# Block_Diagram_V1.net
KiCad netlist of a schematic drawn in EAGLE
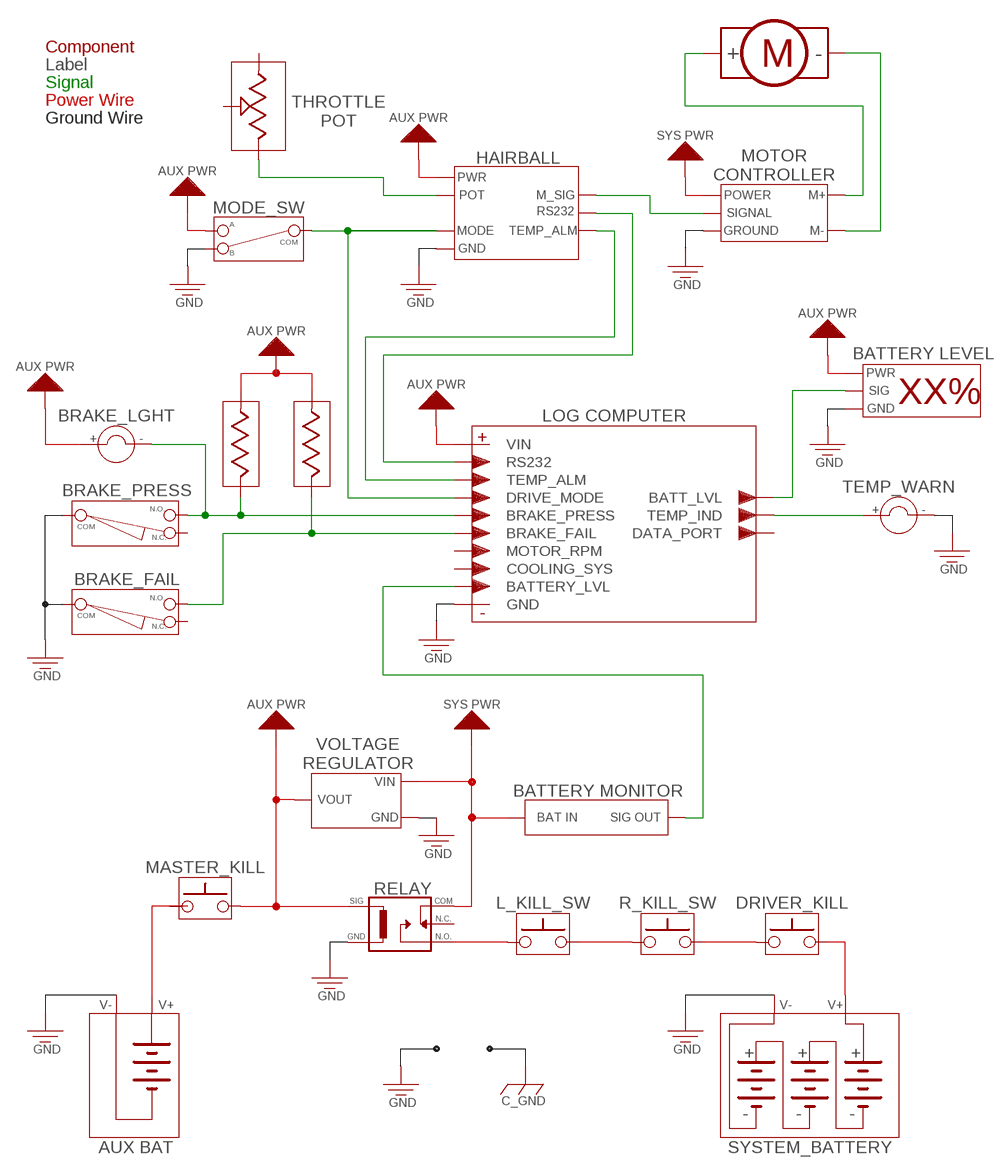
[diagram p0: schematic, sheet 1]

(export (version "E")
  (design (tool "Eeschema 10.0.6"))
  (components
    (comp (ref "BRAKE_FAIL")
      (value "LIMIT_SWITCH")
      (footprint "eagle-import:LIMIT_SWITCH")
      (libsource (lib "eagle-import") (part "LIMIT_SWITCH"))
    )
    (comp (ref "BRAKE_LGHT")
      (value "LIGHT")
      (footprint "eagle-import:LIGHT")
      (libsource (lib "eagle-import") (part "LIGHT"))
    )
    (comp (ref "BRAKE_PRESS")
      (value "LIMIT_SWITCH")
      (footprint "eagle-import:LIMIT_SWITCH")
      (libsource (lib "eagle-import") (part "LIMIT_SWITCH"))
    )
    (comp (ref "DRIVER_KILL")
      (value "BUTTON_SWITCH")
      (footprint "eagle-import:BUTTON_SWITCH")
      (libsource (lib "eagle-import") (part "BUTTON_SWITCH"))
    )
    (comp (ref "L_KILL_SW")
      (value "BUTTON_SWITCH")
      (footprint "eagle-import:BUTTON_SWITCH")
      (libsource (lib "eagle-import") (part "BUTTON_SWITCH"))
    )
    (comp (ref "MASTER_KILL")
      (value "BUTTON_SWITCH")
      (footprint "eagle-import:BUTTON_SWITCH")
      (libsource (lib "eagle-import") (part "BUTTON_SWITCH"))
    )
    (comp (ref "MODE_SW")
      (value "TOGGLE_SWITCH")
      (footprint "eagle-import:TOGGLE_SWITCH")
      (libsource (lib "eagle-import") (part "TOGGLE_SWITCH"))
    )
    (comp (ref "R_KILL_SW")
      (value "BUTTON_SWITCH")
      (footprint "eagle-import:BUTTON_SWITCH")
      (libsource (lib "eagle-import") (part "BUTTON_SWITCH"))
    )
    (comp (ref "TEMP_WARN")
      (value "LIGHT")
      (footprint "eagle-import:LIGHT")
      (libsource (lib "eagle-import") (part "LIGHT"))
    )
    (comp (ref "U$1")
      (value "COMPUTER")
      (footprint "eagle-import:COMPUTER")
      (libsource (lib "eagle-import") (part "COMPUTER"))
    )
    (comp (ref "U$2")
      (value "SYSTEM_BAT")
      (footprint "eagle-import:SYSTEM_BAT")
      (libsource (lib "eagle-import") (part "SYSTEM_BAT"))
    )
    (comp (ref "U$3")
      (value "DC_MOTOR")
      (footprint "eagle-import:DC_MOTOR")
      (libsource (lib "eagle-import") (part "DC_MOTOR"))
    )
    (comp (ref "U$4")
      (value "MOTOR_CONTROLLER")
      (footprint "eagle-import:MOTOR_CONTROLLER")
      (libsource (lib "eagle-import") (part "MOTOR_CONTROLLER"))
    )
    (comp (ref "U$5")
      (value "HAIRBALL")
      (footprint "eagle-import:HAIRBALL")
      (libsource (lib "eagle-import") (part "HAIRBALL"))
    )
    (comp (ref "U$6")
      (value "AUX_PWR")
      (footprint "eagle-import:AUX_PWR")
      (libsource (lib "eagle-import") (part "AUX_PWR"))
    )
    (comp (ref "U$7")
      (value "12V_BAT")
      (footprint "eagle-import:12V_BAT")
      (libsource (lib "eagle-import") (part "12V_BAT"))
    )
    (comp (ref "U$8")
      (value "RELAY")
      (footprint "eagle-import:RELAY")
      (libsource (lib "eagle-import") (part "RELAY"))
    )
    (comp (ref "U$9")
      (value "CHASSIS_GND")
      (footprint "eagle-import:CHASSIS_GND")
      (libsource (lib "eagle-import") (part "CHASSIS_GND"))
    )
    (comp (ref "U$10")
      (value "GND")
      (footprint "eagle-import:GND")
      (libsource (lib "eagle-import") (part "GND"))
    )
    (comp (ref "U$11")
      (value "GND")
      (footprint "eagle-import:GND")
      (libsource (lib "eagle-import") (part "GND"))
    )
    (comp (ref "U$12")
      (value "GND")
      (footprint "eagle-import:GND")
      (libsource (lib "eagle-import") (part "GND"))
    )
    (comp (ref "U$13")
      (value "GND")
      (footprint "eagle-import:GND")
      (libsource (lib "eagle-import") (part "GND"))
    )
    (comp (ref "U$15")
      (value "V_SYS")
      (footprint "eagle-import:V_SYS")
      (libsource (lib "eagle-import") (part "V_SYS"))
    )
    (comp (ref "U$16")
      (value "VOLTAGE_REGULATOR")
      (footprint "eagle-import:VOLTAGE_REGULATOR")
      (libsource (lib "eagle-import") (part "VOLTAGE_REGULATOR"))
    )
    (comp (ref "U$17")
      (value "GND")
      (footprint "eagle-import:GND")
      (libsource (lib "eagle-import") (part "GND"))
    )
    (comp (ref "U$20")
      (value "AUX_PWR")
      (footprint "eagle-import:AUX_PWR")
      (libsource (lib "eagle-import") (part "AUX_PWR"))
    )
    (comp (ref "U$21")
      (value "GND")
      (footprint "eagle-import:GND")
      (libsource (lib "eagle-import") (part "GND"))
    )
    (comp (ref "U$22")
      (value "AUX_PWR")
      (footprint "eagle-import:AUX_PWR")
      (libsource (lib "eagle-import") (part "AUX_PWR"))
    )
    (comp (ref "U$23")
      (value "GND")
      (footprint "eagle-import:GND")
      (libsource (lib "eagle-import") (part "GND"))
    )
    (comp (ref "U$24")
      (value "V_SYS")
      (footprint "eagle-import:V_SYS")
      (libsource (lib "eagle-import") (part "V_SYS"))
    )
    (comp (ref "U$25")
      (value "GND")
      (footprint "eagle-import:GND")
      (libsource (lib "eagle-import") (part "GND"))
    )
    (comp (ref "U$26")
      (value "BATTERY_MONITOR")
      (footprint "eagle-import:BATTERY_MONITOR")
      (libsource (lib "eagle-import") (part "BATTERY_MONITOR"))
    )
    (comp (ref "U$28")
      (value "THROTTLE_POT")
      (footprint "eagle-import:THROTTLE_POT")
      (libsource (lib "eagle-import") (part "THROTTLE_POT"))
    )
    (comp (ref "U$29")
      (value "AUX_PWR")
      (footprint "eagle-import:AUX_PWR")
      (libsource (lib "eagle-import") (part "AUX_PWR"))
    )
    (comp (ref "U$30")
      (value "GND")
      (footprint "eagle-import:GND")
      (libsource (lib "eagle-import") (part "GND"))
    )
    (comp (ref "U$31")
      (value "AUX_PWR")
      (footprint "eagle-import:AUX_PWR")
      (libsource (lib "eagle-import") (part "AUX_PWR"))
    )
    (comp (ref "U$32")
      (value "RESISTOR")
      (footprint "eagle-import:RESISTOR")
      (libsource (lib "eagle-import") (part "RESISTOR"))
    )
    (comp (ref "U$33")
      (value "RESISTOR")
      (footprint "eagle-import:RESISTOR")
      (libsource (lib "eagle-import") (part "RESISTOR"))
    )
    (comp (ref "U$35")
      (value "GND")
      (footprint "eagle-import:GND")
      (libsource (lib "eagle-import") (part "GND"))
    )
    (comp (ref "U$36")
      (value "BATTERY_DISPLAY")
      (footprint "eagle-import:BATTERY_DISPLAY")
      (libsource (lib "eagle-import") (part "BATTERY_DISPLAY"))
    )
    (comp (ref "U$37")
      (value "AUX_PWR")
      (footprint "eagle-import:AUX_PWR")
      (libsource (lib "eagle-import") (part "AUX_PWR"))
    )
    (comp (ref "U$38")
      (value "GND")
      (footprint "eagle-import:GND")
      (libsource (lib "eagle-import") (part "GND"))
    )
    (comp (ref "U$40")
      (value "GND")
      (footprint "eagle-import:GND")
      (libsource (lib "eagle-import") (part "GND"))
    )
    (comp (ref "U$41")
      (value "AUX_PWR")
      (footprint "eagle-import:AUX_PWR")
      (libsource (lib "eagle-import") (part "AUX_PWR"))
    )
  )
  (nets
    (net (code "1") (name "Net-(BRAKE_FAIL-PadNO)") (class "Default")
      (node (ref "BRAKE_FAIL") (pin "NO") (pinfunction "NO_NO") (pintype "bidirectional"))
      (node (ref "U$1") (pin "BRAKE_FAIL") (pinfunction "BRAKE_FAIL_BRAKE_FAIL") (pintype "bidirectional"))
      (node (ref "U$33") (pin "B") (pinfunction "B_B") (pintype "passive"))
    )
    (net (code "2") (name "Net-(BRAKE_LGHT-PadGND)") (class "Default")
      (node (ref "BRAKE_LGHT") (pin "GND") (pinfunction "GND_GND") (pintype "bidirectional"))
      (node (ref "BRAKE_PRESS") (pin "NO") (pinfunction "NO_NO") (pintype "bidirectional"))
      (node (ref "U$1") (pin "BRAKE_PRESS") (pinfunction "BRAKE_PRESS_BRAKE_PRESS") (pintype "bidirectional"))
      (node (ref "U$32") (pin "B") (pinfunction "B_B") (pintype "passive"))
    )
    (net (code "3") (name "Net-(MODE_SW-PadCOM)") (class "Default")
      (node (ref "MODE_SW") (pin "COM") (pinfunction "COM_COM") (pintype "bidirectional"))
      (node (ref "U$1") (pin "DRIVE_MODE") (pinfunction "DRIVE_MODE_DRIVE_MODE") (pintype "bidirectional"))
      (node (ref "U$5") (pin "MODE") (pinfunction "MODE_MODE") (pintype "bidirectional"))
    )
    (net (code "4") (name "Net-(TEMP_WARN-PadVIN)") (class "Default")
      (node (ref "TEMP_WARN") (pin "VIN") (pinfunction "VIN_VIN") (pintype "bidirectional"))
      (node (ref "U$1") (pin "TEMP_IND") (pinfunction "TEMP_IND_TEMP_IND") (pintype "bidirectional"))
    )
    (net (code "5") (name "Net-(U$1-PadBATTERY_LVL)") (class "Default")
      (node (ref "U$1") (pin "BATTERY_LVL") (pinfunction "BATTERY_LVL_BATTERY_LVL") (pintype "bidirectional"))
      (node (ref "U$26") (pin "SIG") (pinfunction "SIG_SIG") (pintype "bidirectional"))
    )
    (net (code "6") (name "Net-(U$1-PadBATT_LVL)") (class "Default")
      (node (ref "U$1") (pin "BATT_LVL") (pinfunction "BATT_LVL_BATT_LVL") (pintype "bidirectional"))
      (node (ref "U$36") (pin "SIG") (pinfunction "SIG_SIG") (pintype "bidirectional"))
    )
    (net (code "7") (name "Net-(U$1-PadRS232)") (class "Default")
      (node (ref "U$1") (pin "RS232") (pinfunction "RS232_RS232") (pintype "bidirectional"))
      (node (ref "U$5") (pin "RS232") (pinfunction "RS232_RS232") (pintype "bidirectional"))
    )
    (net (code "8") (name "Net-(U$1-PadTEMP_ALM)") (class "Default")
      (node (ref "U$1") (pin "TEMP_ALM") (pinfunction "TEMP_ALM_TEMP_ALM") (pintype "bidirectional"))
      (node (ref "U$5") (pin "OVERTEMP") (pinfunction "OVERTEMP_OVERTEMP") (pintype "bidirectional"))
    )
    (net (code "9") (name "Net-(U$3-Pad+)") (class "Default")
      (node (ref "U$3") (pin "+") (pinfunction "+_+") (pintype "bidirectional"))
      (node (ref "U$4") (pin "M+") (pinfunction "M+_M+") (pintype "bidirectional"))
    )
    (net (code "10") (name "Net-(U$3-Pad-)") (class "Default")
      (node (ref "U$3") (pin "-") (pinfunction "-_-") (pintype "bidirectional"))
      (node (ref "U$4") (pin "M-") (pinfunction "M-_M-") (pintype "bidirectional"))
    )
    (net (code "11") (name "Net-(U$5-MOTOR_SIG)") (class "Default")
      (node (ref "U$4") (pin "SIG") (pinfunction "SIG_SIG") (pintype "bidirectional"))
      (node (ref "U$5") (pin "M_SIG") (pinfunction "MOTOR_SIG_M_SIG") (pintype "bidirectional"))
    )
    (net (code "12") (name "Net-(U$28-PadV-)") (class "Default")
      (node (ref "U$28") (pin "V-") (pinfunction "V-_V-") (pintype "passive"))
      (node (ref "U$5") (pin "THROTTLE_POT") (pinfunction "THROTTLE_POT_THROTTLE_POT") (pintype "bidirectional"))
    )
    (net (code "13") (name "unconnected-(BRAKE_FAIL-PadCOM)") (class "Default")
      (node (ref "BRAKE_FAIL") (pin "COM") (pinfunction "COM_COM") (pintype "bidirectional"))
    )
    (net (code "14") (name "unconnected-(BRAKE_FAIL-PadNC)") (class "Default")
      (node (ref "BRAKE_FAIL") (pin "NC") (pinfunction "NC_NC") (pintype "bidirectional"))
    )
    (net (code "15") (name "unconnected-(BRAKE_LGHT-PadVIN)") (class "Default")
      (node (ref "BRAKE_LGHT") (pin "VIN") (pinfunction "VIN_VIN") (pintype "bidirectional"))
    )
    (net (code "16") (name "unconnected-(BRAKE_PRESS-PadCOM)") (class "Default")
      (node (ref "BRAKE_PRESS") (pin "COM") (pinfunction "COM_COM") (pintype "bidirectional"))
    )
    (net (code "17") (name "unconnected-(BRAKE_PRESS-PadNC)") (class "Default")
      (node (ref "BRAKE_PRESS") (pin "NC") (pinfunction "NC_NC") (pintype "bidirectional"))
    )
    (net (code "18") (name "unconnected-(DRIVER_KILL-PadA)") (class "Default")
      (node (ref "DRIVER_KILL") (pin "A") (pinfunction "A_A") (pintype "bidirectional"))
    )
    (net (code "19") (name "unconnected-(DRIVER_KILL-PadB)") (class "Default")
      (node (ref "DRIVER_KILL") (pin "B") (pinfunction "B_B") (pintype "bidirectional"))
    )
    (net (code "20") (name "unconnected-(L_KILL_SW-PadA)") (class "Default")
      (node (ref "L_KILL_SW") (pin "A") (pinfunction "A_A") (pintype "bidirectional"))
    )
    (net (code "21") (name "unconnected-(L_KILL_SW-PadB)") (class "Default")
      (node (ref "L_KILL_SW") (pin "B") (pinfunction "B_B") (pintype "bidirectional"))
    )
    (net (code "22") (name "unconnected-(MASTER_KILL-PadA)") (class "Default")
      (node (ref "MASTER_KILL") (pin "A") (pinfunction "A_A") (pintype "bidirectional"))
    )
    (net (code "23") (name "unconnected-(MASTER_KILL-PadB)") (class "Default")
      (node (ref "MASTER_KILL") (pin "B") (pinfunction "B_B") (pintype "bidirectional"))
    )
    (net (code "24") (name "unconnected-(MODE_SW-PadPOS_A)") (class "Default")
      (node (ref "MODE_SW") (pin "POS_A") (pinfunction "POS_A_POS_A") (pintype "bidirectional"))
    )
    (net (code "25") (name "unconnected-(MODE_SW-PadPOS_B)") (class "Default")
      (node (ref "MODE_SW") (pin "POS_B") (pinfunction "POS_B_POS_B") (pintype "bidirectional"))
    )
    (net (code "26") (name "unconnected-(R_KILL_SW-PadA)") (class "Default")
      (node (ref "R_KILL_SW") (pin "A") (pinfunction "A_A") (pintype "bidirectional"))
    )
    (net (code "27") (name "unconnected-(R_KILL_SW-PadB)") (class "Default")
      (node (ref "R_KILL_SW") (pin "B") (pinfunction "B_B") (pintype "bidirectional"))
    )
    (net (code "28") (name "unconnected-(TEMP_WARN-PadGND)") (class "Default")
      (node (ref "TEMP_WARN") (pin "GND") (pinfunction "GND_GND") (pintype "bidirectional"))
    )
    (net (code "29") (name "unconnected-(U$1-DATA_PORT-PadDATAPORT)") (class "Default")
      (node (ref "U$1") (pin "DATAPORT") (pinfunction "DATA_PORT_DATAPORT") (pintype "bidirectional"))
    )
    (net (code "30") (name "unconnected-(U$1-PadCOOLING_SYS)") (class "Default")
      (node (ref "U$1") (pin "COOLING_SYS") (pinfunction "COOLING_SYS_COOLING_SYS") (pintype "bidirectional"))
    )
    (net (code "31") (name "unconnected-(U$1-PadGND)") (class "Default")
      (node (ref "U$1") (pin "GND") (pinfunction "GND_GND") (pintype "bidirectional"))
    )
    (net (code "32") (name "unconnected-(U$1-PadMOTOR_RPM)") (class "Default")
      (node (ref "U$1") (pin "MOTOR_RPM") (pinfunction "MOTOR_RPM_MOTOR_RPM") (pintype "bidirectional"))
    )
    (net (code "33") (name "unconnected-(U$1-VIN-PadPWR)") (class "Default")
      (node (ref "U$1") (pin "PWR") (pinfunction "VIN_PWR") (pintype "bidirectional"))
    )
    (net (code "34") (name "unconnected-(U$2-PadV+)") (class "Default")
      (node (ref "U$2") (pin "V+") (pinfunction "V+_V+") (pintype "passive"))
    )
    (net (code "35") (name "unconnected-(U$2-PadV-)") (class "Default")
      (node (ref "U$2") (pin "V-") (pinfunction "V-_V-") (pintype "passive"))
    )
    (net (code "36") (name "unconnected-(U$4-PadGND)") (class "Default")
      (node (ref "U$4") (pin "GND") (pinfunction "GND_GND") (pintype "bidirectional"))
    )
    (net (code "37") (name "unconnected-(U$4-PadPWR)") (class "Default")
      (node (ref "U$4") (pin "PWR") (pinfunction "PWR_PWR") (pintype "bidirectional"))
    )
    (net (code "38") (name "unconnected-(U$5-PadGND)") (class "Default")
      (node (ref "U$5") (pin "GND") (pinfunction "GND_GND") (pintype "bidirectional"))
    )
    (net (code "39") (name "unconnected-(U$5-PadPWR)") (class "Default")
      (node (ref "U$5") (pin "PWR") (pinfunction "PWR_PWR") (pintype "bidirectional"))
    )
    (net (code "40") (name "unconnected-(U$6-PadAUX_PWR)") (class "Default")
      (node (ref "U$6") (pin "AUX_PWR") (pinfunction "AUX_PWR_AUX_PWR") (pintype "bidirectional"))
    )
    (net (code "41") (name "unconnected-(U$7-Pad+12V)") (class "Default")
      (node (ref "U$7") (pin "+12V") (pinfunction "+12V_+12V") (pintype "bidirectional"))
    )
    (net (code "42") (name "unconnected-(U$7-PadGND)") (class "Default")
      (node (ref "U$7") (pin "GND") (pinfunction "GND_GND") (pintype "bidirectional"))
    )
    (net (code "43") (name "unconnected-(U$8-PadCOM)") (class "Default")
      (node (ref "U$8") (pin "COM") (pinfunction "COM_COM") (pintype "bidirectional"))
    )
    (net (code "44") (name "unconnected-(U$8-PadGND)") (class "Default")
      (node (ref "U$8") (pin "GND") (pinfunction "GND_GND") (pintype "bidirectional"))
    )
    (net (code "45") (name "unconnected-(U$8-PadNC)") (class "Default")
      (node (ref "U$8") (pin "NC") (pinfunction "NC_NC") (pintype "bidirectional"))
    )
    (net (code "46") (name "unconnected-(U$8-PadNO)") (class "Default")
      (node (ref "U$8") (pin "NO") (pinfunction "NO_NO") (pintype "bidirectional"))
    )
    (net (code "47") (name "unconnected-(U$8-PadSIG)") (class "Default")
      (node (ref "U$8") (pin "SIG") (pinfunction "SIG_SIG") (pintype "bidirectional"))
    )
    (net (code "48") (name "unconnected-(U$9-PadC_GND)") (class "Default")
      (node (ref "U$9") (pin "C_GND") (pinfunction "C_GND_C_GND") (pintype "bidirectional"))
    )
    (net (code "49") (name "unconnected-(U$10-PadGND)") (class "Default")
      (node (ref "U$10") (pin "GND") (pinfunction "GND_GND") (pintype "bidirectional"))
    )
    (net (code "50") (name "unconnected-(U$11-PadGND)") (class "Default")
      (node (ref "U$11") (pin "GND") (pinfunction "GND_GND") (pintype "bidirectional"))
    )
    (net (code "51") (name "unconnected-(U$12-PadGND)") (class "Default")
      (node (ref "U$12") (pin "GND") (pinfunction "GND_GND") (pintype "bidirectional"))
    )
    (net (code "52") (name "unconnected-(U$13-PadGND)") (class "Default")
      (node (ref "U$13") (pin "GND") (pinfunction "GND_GND") (pintype "bidirectional"))
    )
    (net (code "53") (name "unconnected-(U$15-PadV_SYS)") (class "Default")
      (node (ref "U$15") (pin "V_SYS") (pinfunction "V_SYS_V_SYS") (pintype "bidirectional"))
    )
    (net (code "54") (name "unconnected-(U$16-PadGND)") (class "Default")
      (node (ref "U$16") (pin "GND") (pinfunction "GND_GND") (pintype "bidirectional"))
    )
    (net (code "55") (name "unconnected-(U$16-PadVIN)") (class "Default")
      (node (ref "U$16") (pin "VIN") (pinfunction "VIN_VIN") (pintype "bidirectional"))
    )
    (net (code "56") (name "unconnected-(U$16-PadVOUT)") (class "Default")
      (node (ref "U$16") (pin "VOUT") (pinfunction "VOUT_VOUT") (pintype "bidirectional"))
    )
    (net (code "57") (name "unconnected-(U$17-PadGND)") (class "Default")
      (node (ref "U$17") (pin "GND") (pinfunction "GND_GND") (pintype "bidirectional"))
    )
    (net (code "58") (name "unconnected-(U$20-PadAUX_PWR)") (class "Default")
      (node (ref "U$20") (pin "AUX_PWR") (pinfunction "AUX_PWR_AUX_PWR") (pintype "bidirectional"))
    )
    (net (code "59") (name "unconnected-(U$21-PadGND)") (class "Default")
      (node (ref "U$21") (pin "GND") (pinfunction "GND_GND") (pintype "bidirectional"))
    )
    (net (code "60") (name "unconnected-(U$22-PadAUX_PWR)") (class "Default")
      (node (ref "U$22") (pin "AUX_PWR") (pinfunction "AUX_PWR_AUX_PWR") (pintype "bidirectional"))
    )
    (net (code "61") (name "unconnected-(U$23-PadGND)") (class "Default")
      (node (ref "U$23") (pin "GND") (pinfunction "GND_GND") (pintype "bidirectional"))
    )
    (net (code "62") (name "unconnected-(U$24-PadV_SYS)") (class "Default")
      (node (ref "U$24") (pin "V_SYS") (pinfunction "V_SYS_V_SYS") (pintype "bidirectional"))
    )
    (net (code "63") (name "unconnected-(U$25-PadGND)") (class "Default")
      (node (ref "U$25") (pin "GND") (pinfunction "GND_GND") (pintype "bidirectional"))
    )
    (net (code "64") (name "unconnected-(U$26-PadBAT)") (class "Default")
      (node (ref "U$26") (pin "BAT") (pinfunction "BAT_BAT") (pintype "bidirectional"))
    )
    (net (code "65") (name "unconnected-(U$28-PadADJ)") (class "Default")
      (node (ref "U$28") (pin "ADJ") (pinfunction "ADJ_ADJ") (pintype "passive"))
    )
    (net (code "66") (name "unconnected-(U$28-PadV+)") (class "Default")
      (node (ref "U$28") (pin "V+") (pinfunction "V+_V+") (pintype "passive"))
    )
    (net (code "67") (name "unconnected-(U$29-PadAUX_PWR)") (class "Default")
      (node (ref "U$29") (pin "AUX_PWR") (pinfunction "AUX_PWR_AUX_PWR") (pintype "bidirectional"))
    )
    (net (code "68") (name "unconnected-(U$30-PadGND)") (class "Default")
      (node (ref "U$30") (pin "GND") (pinfunction "GND_GND") (pintype "bidirectional"))
    )
    (net (code "69") (name "unconnected-(U$31-PadAUX_PWR)") (class "Default")
      (node (ref "U$31") (pin "AUX_PWR") (pinfunction "AUX_PWR_AUX_PWR") (pintype "bidirectional"))
    )
    (net (code "70") (name "unconnected-(U$32-PadA)") (class "Default")
      (node (ref "U$32") (pin "A") (pinfunction "A_A") (pintype "passive"))
    )
    (net (code "71") (name "unconnected-(U$33-PadA)") (class "Default")
      (node (ref "U$33") (pin "A") (pinfunction "A_A") (pintype "passive"))
    )
    (net (code "72") (name "unconnected-(U$35-PadGND)") (class "Default")
      (node (ref "U$35") (pin "GND") (pinfunction "GND_GND") (pintype "bidirectional"))
    )
    (net (code "73") (name "unconnected-(U$36-PadGND)") (class "Default")
      (node (ref "U$36") (pin "GND") (pinfunction "GND_GND") (pintype "bidirectional"))
    )
    (net (code "74") (name "unconnected-(U$36-PadPWR)") (class "Default")
      (node (ref "U$36") (pin "PWR") (pinfunction "PWR_PWR") (pintype "bidirectional"))
    )
    (net (code "75") (name "unconnected-(U$37-PadAUX_PWR)") (class "Default")
      (node (ref "U$37") (pin "AUX_PWR") (pinfunction "AUX_PWR_AUX_PWR") (pintype "bidirectional"))
    )
    (net (code "76") (name "unconnected-(U$38-PadGND)") (class "Default")
      (node (ref "U$38") (pin "GND") (pinfunction "GND_GND") (pintype "bidirectional"))
    )
    (net (code "77") (name "unconnected-(U$40-PadGND)") (class "Default")
      (node (ref "U$40") (pin "GND") (pinfunction "GND_GND") (pintype "bidirectional"))
    )
    (net (code "78") (name "unconnected-(U$41-PadAUX_PWR)") (class "Default")
      (node (ref "U$41") (pin "AUX_PWR") (pinfunction "AUX_PWR_AUX_PWR") (pintype "bidirectional"))
    )
  )
)
